# ay-stereo.net
KiCad netlist of a schematic drawn in EAGLE
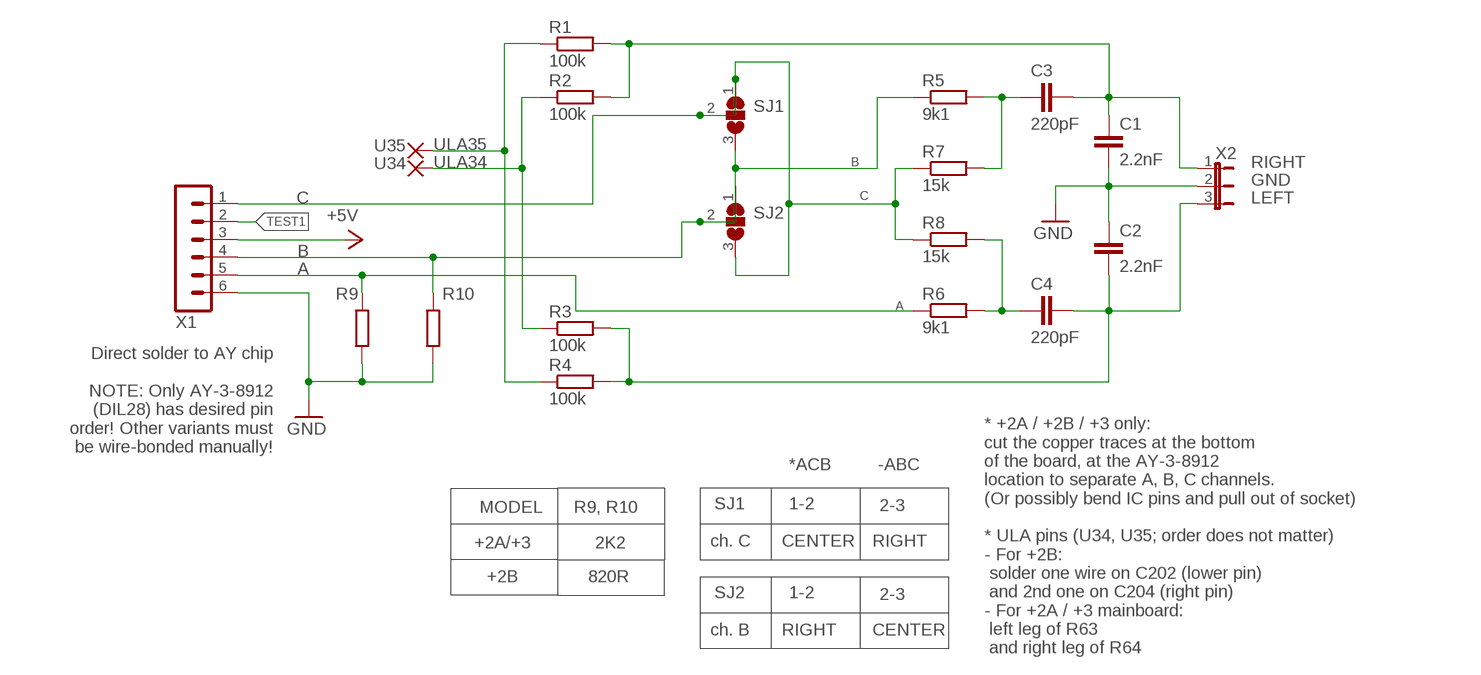
[diagram p0: schematic, sheet 1]

(export (version "E")
  (design (tool "Eeschema 10.0.6"))
  (components
    (comp (ref "C1")
      (value "2.2nF")
      (footprint "eagle-import:C0805")
      (libsource (lib "eagle-import") (part "C-EUC0805"))
    )
    (comp (ref "C2")
      (value "2.2nF")
      (footprint "eagle-import:C0805")
      (libsource (lib "eagle-import") (part "C-EUC0805"))
    )
    (comp (ref "C3")
      (value "220pF")
      (footprint "eagle-import:C0805")
      (libsource (lib "eagle-import") (part "C-EUC0805"))
    )
    (comp (ref "C4")
      (value "220pF")
      (footprint "eagle-import:C0805")
      (libsource (lib "eagle-import") (part "C-EUC0805"))
    )
    (comp (ref "R1")
      (value "100k")
      (footprint "eagle-import:R0805")
      (libsource (lib "eagle-import") (part "R-EU_R0805"))
    )
    (comp (ref "R2")
      (value "100k")
      (footprint "eagle-import:R0805")
      (libsource (lib "eagle-import") (part "R-EU_R0805"))
    )
    (comp (ref "R3")
      (value "100k")
      (footprint "eagle-import:R0805")
      (libsource (lib "eagle-import") (part "R-EU_R0805"))
    )
    (comp (ref "R4")
      (value "100k")
      (footprint "eagle-import:R0805")
      (libsource (lib "eagle-import") (part "R-EU_R0805"))
    )
    (comp (ref "R5")
      (value "9k1")
      (footprint "eagle-import:R0805")
      (libsource (lib "eagle-import") (part "R-EU_R0805"))
    )
    (comp (ref "R6")
      (value "9k1")
      (footprint "eagle-import:R0805")
      (libsource (lib "eagle-import") (part "R-EU_R0805"))
    )
    (comp (ref "R7")
      (value "15k")
      (footprint "eagle-import:R0805")
      (libsource (lib "eagle-import") (part "R-EU_R0805"))
    )
    (comp (ref "R8")
      (value "15k")
      (footprint "eagle-import:R0805")
      (libsource (lib "eagle-import") (part "R-EU_R0805"))
    )
    (comp (ref "R9")
      (value "R-EU_R0805")
      (footprint "eagle-import:R0805")
      (libsource (lib "eagle-import") (part "R-EU_R0805"))
    )
    (comp (ref "R10")
      (value "R-EU_R0805")
      (footprint "eagle-import:R0805")
      (libsource (lib "eagle-import") (part "R-EU_R0805"))
    )
    (comp (ref "SJ1")
      (value "SJ2W")
      (footprint "eagle-import:SJ_2")
      (libsource (lib "eagle-import") (part "SJ2W"))
    )
    (comp (ref "SJ2")
      (value "SJ2W")
      (footprint "eagle-import:SJ_2")
      (libsource (lib "eagle-import") (part "SJ2W"))
    )
    (comp (ref "U34")
      (value "1,6/0,8")
      (footprint "eagle-import:1,6_0,8")
      (libsource (lib "eagle-import") (part "1,6/0,8"))
    )
    (comp (ref "U35")
      (value "1,6/0,8")
      (footprint "eagle-import:1,6_0,8")
      (libsource (lib "eagle-import") (part "1,6/0,8"))
    )
    (comp (ref "X1")
      (value "MA06-1")
      (footprint "eagle-import:MA06-1")
      (libsource (lib "eagle-import") (part "MA06-1"))
    )
    (comp (ref "X2")
      (value "JP2E")
      (footprint "eagle-import:JP2")
      (libsource (lib "eagle-import") (part "JP2E"))
    )
  )
  (nets
    (net (code "1") (name "+5V") (class "Default")
      (node (ref "X1") (pin "3") (pinfunction "3_3") (pintype "passive"))
    )
    (net (code "2") (name "/A") (class "Default")
      (node (ref "R6") (pin "1") (pinfunction "1_1") (pintype "passive"))
      (node (ref "R9") (pin "2") (pinfunction "2_2") (pintype "passive"))
      (node (ref "X1") (pin "5") (pinfunction "5_5") (pintype "passive"))
    )
    (net (code "3") (name "/B") (class "Default")
      (node (ref "R10") (pin "2") (pinfunction "2_2") (pintype "passive"))
      (node (ref "R5") (pin "1") (pinfunction "1_1") (pintype "passive"))
      (node (ref "SJ1") (pin "3") (pinfunction "3_3") (pintype "passive"))
      (node (ref "SJ2") (pin "1") (pinfunction "1_1") (pintype "passive"))
      (node (ref "SJ2") (pin "2") (pinfunction "2_2") (pintype "passive"))
      (node (ref "X1") (pin "4") (pinfunction "4_4") (pintype "passive"))
    )
    (net (code "4") (name "/C") (class "Default")
      (node (ref "R7") (pin "1") (pinfunction "1_1") (pintype "passive"))
      (node (ref "R8") (pin "1") (pinfunction "1_1") (pintype "passive"))
      (node (ref "SJ1") (pin "1") (pinfunction "1_1") (pintype "passive"))
      (node (ref "SJ1") (pin "2") (pinfunction "2_2") (pintype "passive"))
      (node (ref "SJ2") (pin "3") (pinfunction "3_3") (pintype "passive"))
      (node (ref "X1") (pin "1") (pinfunction "1_1") (pintype "passive"))
    )
    (net (code "5") (name "/LEFT") (class "Default")
      (node (ref "C2") (pin "2") (pinfunction "2_2") (pintype "passive"))
      (node (ref "C4") (pin "2") (pinfunction "2_2") (pintype "passive"))
      (node (ref "R3") (pin "2") (pinfunction "2_2") (pintype "passive"))
      (node (ref "R4") (pin "2") (pinfunction "2_2") (pintype "passive"))
      (node (ref "X2") (pin "3") (pinfunction "3_3") (pintype "passive"))
    )
    (net (code "6") (name "/RIGHT") (class "Default")
      (node (ref "C1") (pin "1") (pinfunction "1_1") (pintype "passive"))
      (node (ref "C3") (pin "2") (pinfunction "2_2") (pintype "passive"))
      (node (ref "R1") (pin "2") (pinfunction "2_2") (pintype "passive"))
      (node (ref "R2") (pin "2") (pinfunction "2_2") (pintype "passive"))
      (node (ref "X2") (pin "1") (pinfunction "1_1") (pintype "passive"))
    )
    (net (code "7") (name "/ULA34") (class "Default")
      (node (ref "R2") (pin "1") (pinfunction "1_1") (pintype "passive"))
      (node (ref "R3") (pin "1") (pinfunction "1_1") (pintype "passive"))
      (node (ref "U34") (pin "1") (pinfunction "P_1") (pintype "passive"))
    )
    (net (code "8") (name "/ULA35") (class "Default")
      (node (ref "R1") (pin "1") (pinfunction "1_1") (pintype "passive"))
      (node (ref "R4") (pin "1") (pinfunction "1_1") (pintype "passive"))
      (node (ref "U35") (pin "1") (pinfunction "P_1") (pintype "passive"))
    )
    (net (code "9") (name "GND") (class "Default")
      (node (ref "C1") (pin "2") (pinfunction "2_2") (pintype "passive"))
      (node (ref "C2") (pin "1") (pinfunction "1_1") (pintype "passive"))
      (node (ref "R10") (pin "1") (pinfunction "1_1") (pintype "passive"))
      (node (ref "R9") (pin "1") (pinfunction "1_1") (pintype "passive"))
      (node (ref "X1") (pin "6") (pinfunction "6_6") (pintype "passive"))
      (node (ref "X2") (pin "2") (pinfunction "2_2") (pintype "passive"))
    )
    (net (code "10") (name "Net-(C3-Pad1)") (class "Default")
      (node (ref "C3") (pin "1") (pinfunction "1_1") (pintype "passive"))
      (node (ref "R5") (pin "2") (pinfunction "2_2") (pintype "passive"))
      (node (ref "R7") (pin "2") (pinfunction "2_2") (pintype "passive"))
    )
    (net (code "11") (name "Net-(C4-Pad1)") (class "Default")
      (node (ref "C4") (pin "1") (pinfunction "1_1") (pintype "passive"))
      (node (ref "R6") (pin "2") (pinfunction "2_2") (pintype "passive"))
      (node (ref "R8") (pin "2") (pinfunction "2_2") (pintype "passive"))
    )
    (net (code "12") (name "TEST1") (class "Default")
      (node (ref "X1") (pin "2") (pinfunction "2_2") (pintype "passive"))
    )
  )
)
